# akabeacon_circle_MDBT40.net
KiCad netlist of a schematic drawn in EAGLE
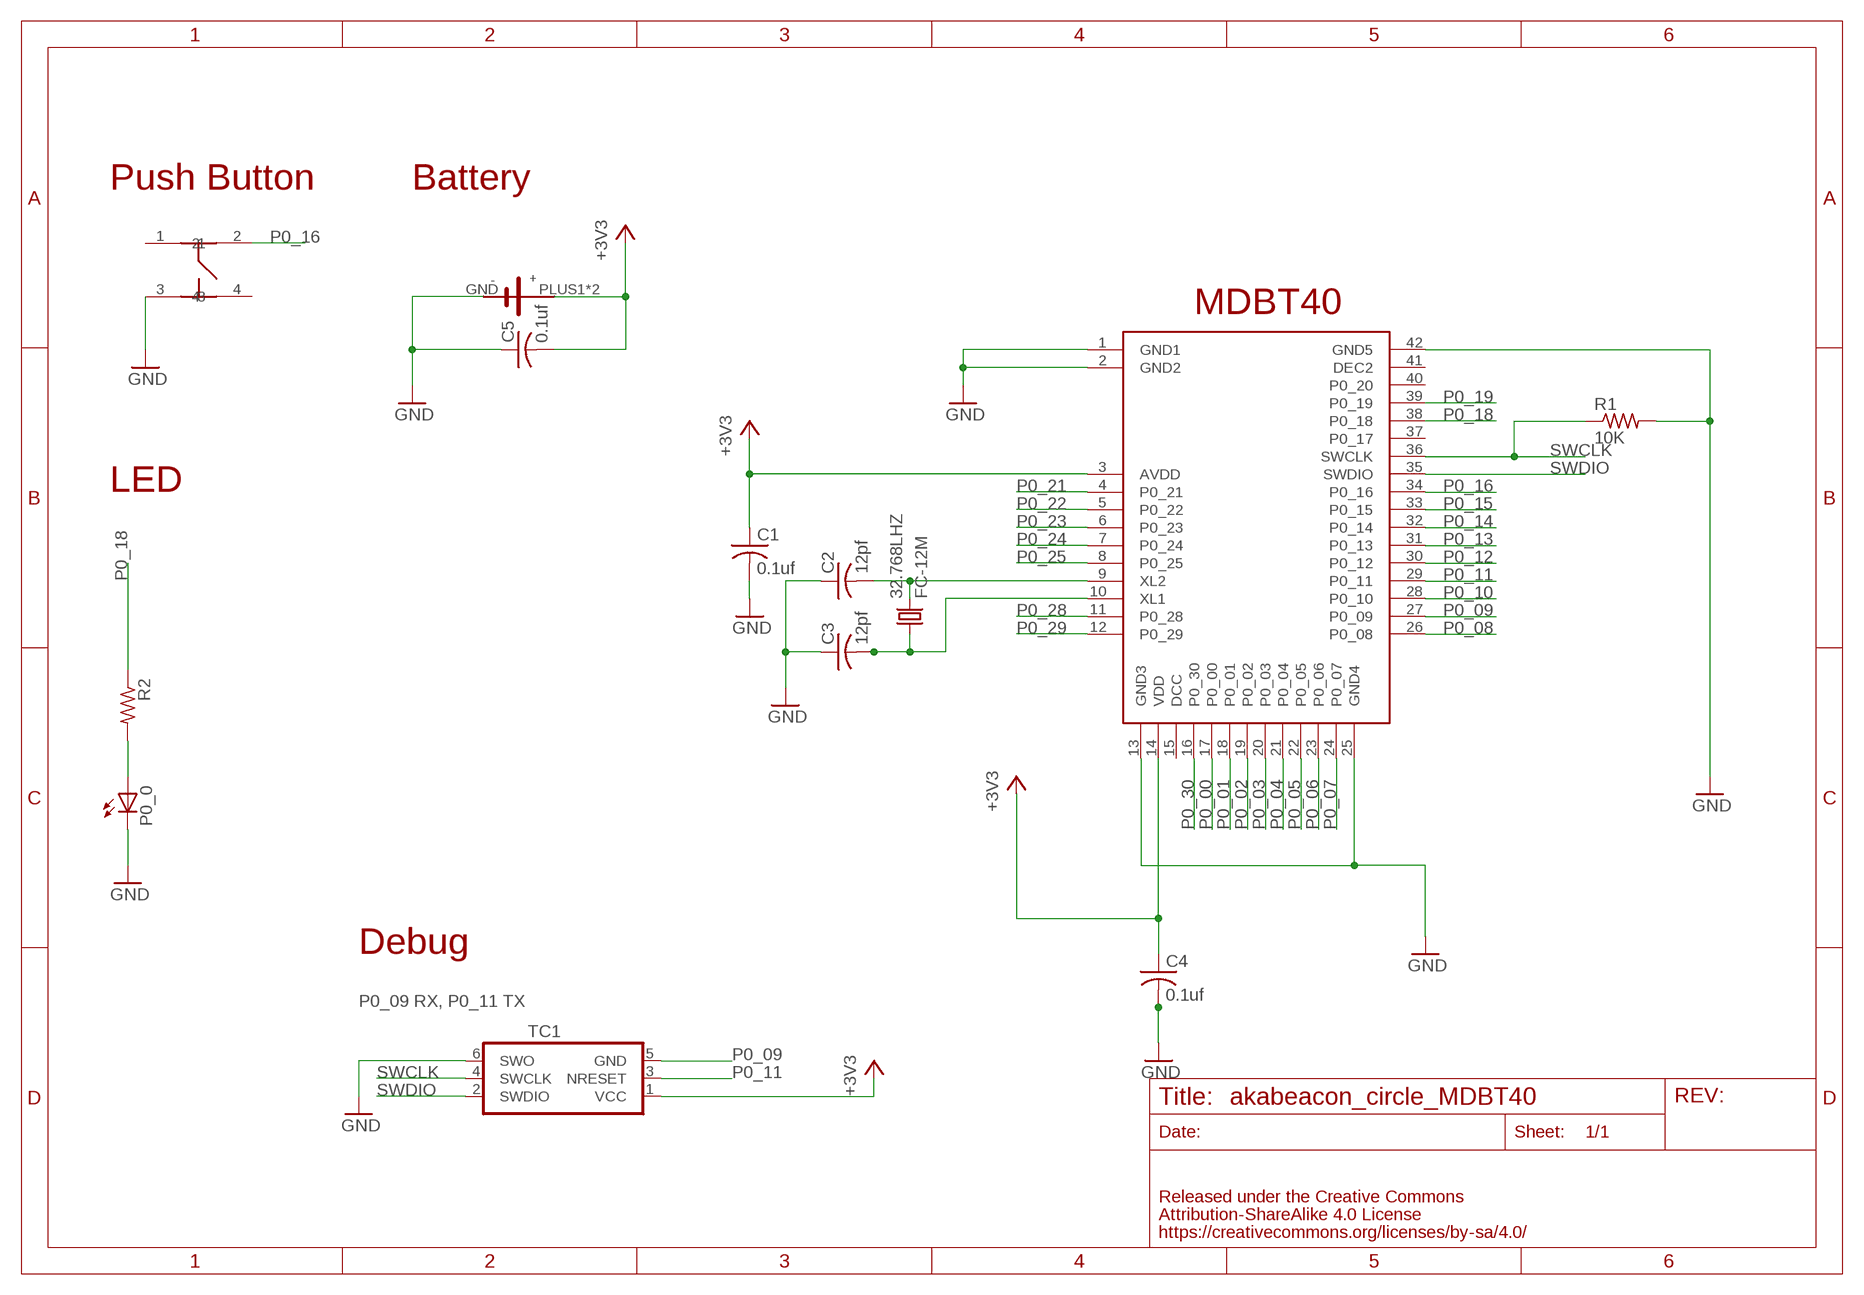
[diagram p0: schematic, sheet 1]

(export (version "E")
  (design (tool "Eeschema 10.0.6"))
  (components
    (comp (ref "32.768LHZ")
      (value "FC-12M")
      (footprint "eagle-import:FC-12M")
      (libsource (lib "eagle-import") (part "FC-12M"))
    )
    (comp (ref "C1")
      (value "0.1uf")
      (footprint "eagle-import:C0603")
      (libsource (lib "eagle-import") (part "C-USC0603"))
    )
    (comp (ref "C2")
      (value "12pf")
      (footprint "eagle-import:C0603")
      (libsource (lib "eagle-import") (part "C-USC0603"))
    )
    (comp (ref "C3")
      (value "12pf")
      (footprint "eagle-import:C0603")
      (libsource (lib "eagle-import") (part "C-USC0603"))
    )
    (comp (ref "C4")
      (value "0.1uf")
      (footprint "eagle-import:C0603")
      (libsource (lib "eagle-import") (part "C-USC0603"))
    )
    (comp (ref "C5")
      (value "0.1uf")
      (footprint "eagle-import:C0603")
      (libsource (lib "eagle-import") (part "C-USC0603"))
    )
    (comp (ref "P0_0")
      (value "LEDCHIP-LED0603")
      (footprint "eagle-import:CHIP-LED0603")
      (libsource (lib "eagle-import") (part "LEDCHIP-LED0603"))
    )
    (comp (ref "R1")
      (value "10K")
      (footprint "eagle-import:R0603")
      (libsource (lib "eagle-import") (part "R-US_R0603"))
    )
    (comp (ref "R2")
      (value "R-US_R0603")
      (footprint "eagle-import:R0603")
      (libsource (lib "eagle-import") (part "R-US_R0603"))
    )
    (comp (ref "TC1")
      (value "TC2030-IDC-NL")
      (footprint "eagle-import:TC2030-IDC-NL")
      (libsource (lib "eagle-import") (part "TC2030-IDC-NL"))
    )
    (comp (ref "U$1")
      (value "RAYTAC-MDBT40")
      (footprint "eagle-import:RAYTAC-MDBT40")
      (libsource (lib "eagle-import") (part "RAYTAC-MDBT40"))
    )
    (comp (ref "U$5")
      (value "SWICTH-4P(KMR2)")
      (footprint "eagle-import:SWITCH-4P(KMR2)")
      (libsource (lib "eagle-import") (part "SWICTH-4P(KMR2)"))
    )
    (comp (ref "U$7")
      (value "CIRCLE-TYPE1")
      (footprint "eagle-import:CIRCLE-TYE1-TC2030")
      (libsource (lib "eagle-import") (part "CIRCLE-TYPE1"))
    )
  )
  (nets
    (net (code "1") (name "+3V3") (class "Default")
      (node (ref "C1") (pin "1") (pinfunction "1_1") (pintype "passive"))
      (node (ref "C4") (pin "1") (pinfunction "1_1") (pintype "passive"))
      (node (ref "C5") (pin "2") (pinfunction "2_2") (pintype "passive"))
      (node (ref "TC1") (pin "1") (pinfunction "VCC_1") (pintype "passive"))
      (node (ref "U$1") (pin "14") (pinfunction "VDD_14") (pintype "bidirectional"))
      (node (ref "U$1") (pin "3") (pinfunction "AVDD_3") (pintype "bidirectional"))
      (node (ref "U$7") (pin "PLUS1") (pinfunction "VCC_PLUS1") (pintype "bidirectional"))
      (node (ref "U$7") (pin "PLUS2") (pinfunction "VCC_PLUS2") (pintype "bidirectional"))
    )
    (net (code "2") (name "/P0_00") (class "Default")
      (node (ref "U$1") (pin "17") (pinfunction "P0_00_17") (pintype "bidirectional"))
    )
    (net (code "3") (name "/P0_01") (class "Default")
      (node (ref "U$1") (pin "18") (pinfunction "P0_01_18") (pintype "bidirectional"))
    )
    (net (code "4") (name "/P0_02") (class "Default")
      (node (ref "U$1") (pin "19") (pinfunction "P0_02_19") (pintype "bidirectional"))
    )
    (net (code "5") (name "/P0_03") (class "Default")
      (node (ref "U$1") (pin "20") (pinfunction "P0_03_20") (pintype "bidirectional"))
    )
    (net (code "6") (name "/P0_04") (class "Default")
      (node (ref "U$1") (pin "21") (pinfunction "P0_04_21") (pintype "bidirectional"))
    )
    (net (code "7") (name "/P0_05") (class "Default")
      (node (ref "U$1") (pin "22") (pinfunction "P0_05_22") (pintype "bidirectional"))
    )
    (net (code "8") (name "/P0_06") (class "Default")
      (node (ref "U$1") (pin "23") (pinfunction "P0_06_23") (pintype "bidirectional"))
    )
    (net (code "9") (name "/P0_07") (class "Default")
      (node (ref "U$1") (pin "24") (pinfunction "P0_07_24") (pintype "bidirectional"))
    )
    (net (code "10") (name "/P0_08") (class "Default")
      (node (ref "U$1") (pin "26") (pinfunction "P0_08_26") (pintype "bidirectional"))
    )
    (net (code "11") (name "/P0_09") (class "Default")
      (node (ref "TC1") (pin "5") (pinfunction "GND_5") (pintype "passive"))
      (node (ref "U$1") (pin "27") (pinfunction "P0_09_27") (pintype "bidirectional"))
    )
    (net (code "12") (name "/P0_10") (class "Default")
      (node (ref "U$1") (pin "28") (pinfunction "P0_10_28") (pintype "bidirectional"))
    )
    (net (code "13") (name "/P0_11") (class "Default")
      (node (ref "TC1") (pin "3") (pinfunction "NRESET_3") (pintype "passive"))
      (node (ref "U$1") (pin "29") (pinfunction "P0_11_29") (pintype "bidirectional"))
    )
    (net (code "14") (name "/P0_12") (class "Default")
      (node (ref "U$1") (pin "30") (pinfunction "P0_12_30") (pintype "bidirectional"))
    )
    (net (code "15") (name "/P0_13") (class "Default")
      (node (ref "U$1") (pin "31") (pinfunction "P0_13_31") (pintype "bidirectional"))
    )
    (net (code "16") (name "/P0_14") (class "Default")
      (node (ref "U$1") (pin "32") (pinfunction "P0_14_32") (pintype "bidirectional"))
    )
    (net (code "17") (name "/P0_15") (class "Default")
      (node (ref "U$1") (pin "33") (pinfunction "P0_15_33") (pintype "bidirectional"))
    )
    (net (code "18") (name "/P0_16") (class "Default")
      (node (ref "U$1") (pin "34") (pinfunction "P0_16_34") (pintype "bidirectional"))
      (node (ref "U$5") (pin "2") (pinfunction "2_2") (pintype "bidirectional"))
    )
    (net (code "19") (name "/P0_18") (class "Default")
      (node (ref "R2") (pin "1") (pinfunction "1_1") (pintype "passive"))
      (node (ref "U$1") (pin "38") (pinfunction "P0_18_38") (pintype "bidirectional"))
    )
    (net (code "20") (name "/P0_19") (class "Default")
      (node (ref "U$1") (pin "39") (pinfunction "P0_19_39") (pintype "bidirectional"))
    )
    (net (code "21") (name "/P0_21") (class "Default")
      (node (ref "U$1") (pin "4") (pinfunction "P0_21_4") (pintype "bidirectional"))
    )
    (net (code "22") (name "/P0_22") (class "Default")
      (node (ref "U$1") (pin "5") (pinfunction "P0_22_5") (pintype "bidirectional"))
    )
    (net (code "23") (name "/P0_23") (class "Default")
      (node (ref "U$1") (pin "6") (pinfunction "P0_23_6") (pintype "bidirectional"))
    )
    (net (code "24") (name "/P0_24") (class "Default")
      (node (ref "U$1") (pin "7") (pinfunction "P0_24_7") (pintype "bidirectional"))
    )
    (net (code "25") (name "/P0_25") (class "Default")
      (node (ref "U$1") (pin "8") (pinfunction "P0_25_8") (pintype "bidirectional"))
    )
    (net (code "26") (name "/P0_28") (class "Default")
      (node (ref "U$1") (pin "11") (pinfunction "P0_28_11") (pintype "bidirectional"))
    )
    (net (code "27") (name "/P0_29") (class "Default")
      (node (ref "U$1") (pin "12") (pinfunction "P0_29_12") (pintype "bidirectional"))
    )
    (net (code "28") (name "/P0_30") (class "Default")
      (node (ref "U$1") (pin "16") (pinfunction "P0_30_16") (pintype "bidirectional"))
    )
    (net (code "29") (name "/SWCLK") (class "Default")
      (node (ref "R1") (pin "1") (pinfunction "1_1") (pintype "passive"))
      (node (ref "TC1") (pin "4") (pinfunction "SWCLK_4") (pintype "passive"))
      (node (ref "U$1") (pin "36") (pinfunction "SWCLK_36") (pintype "bidirectional"))
    )
    (net (code "30") (name "/SWDIO") (class "Default")
      (node (ref "TC1") (pin "2") (pinfunction "SWDIO_2") (pintype "passive"))
      (node (ref "U$1") (pin "35") (pinfunction "SWDIO_35") (pintype "bidirectional"))
    )
    (net (code "31") (name "GND") (class "Default")
      (node (ref "C1") (pin "2") (pinfunction "2_2") (pintype "passive"))
      (node (ref "C2") (pin "1") (pinfunction "1_1") (pintype "passive"))
      (node (ref "C3") (pin "1") (pinfunction "1_1") (pintype "passive"))
      (node (ref "C4") (pin "2") (pinfunction "2_2") (pintype "passive"))
      (node (ref "C5") (pin "1") (pinfunction "1_1") (pintype "passive"))
      (node (ref "P0_0") (pin "C") (pinfunction "C_C") (pintype "passive"))
      (node (ref "R1") (pin "2") (pinfunction "2_2") (pintype "passive"))
      (node (ref "TC1") (pin "6") (pinfunction "SWO_6") (pintype "passive"))
      (node (ref "U$1") (pin "1") (pinfunction "GND1_1") (pintype "bidirectional"))
      (node (ref "U$1") (pin "13") (pinfunction "GND3_13") (pintype "bidirectional"))
      (node (ref "U$1") (pin "2") (pinfunction "GND2_2") (pintype "bidirectional"))
      (node (ref "U$1") (pin "25") (pinfunction "GND4_25") (pintype "bidirectional"))
      (node (ref "U$1") (pin "42") (pinfunction "GND5_42") (pintype "bidirectional"))
      (node (ref "U$5") (pin "3") (pinfunction "3_3") (pintype "bidirectional"))
      (node (ref "U$7") (pin "GND") (pinfunction "GND_GND") (pintype "bidirectional"))
    )
    (net (code "32") (name "Net-(P0_0-PadA)") (class "Default")
      (node (ref "P0_0") (pin "A") (pinfunction "A_A") (pintype "passive"))
      (node (ref "R2") (pin "2") (pinfunction "2_2") (pintype "passive"))
    )
    (net (code "33") (name "Net-(U$1-XL1)") (class "Default")
      (node (ref "32.768LHZ") (pin "1") (pinfunction "1_1") (pintype "passive"))
      (node (ref "C3") (pin "2") (pinfunction "2_2") (pintype "passive"))
      (node (ref "U$1") (pin "10") (pinfunction "XL1_10") (pintype "bidirectional"))
    )
    (net (code "34") (name "Net-(U$1-XL2)") (class "Default")
      (node (ref "32.768LHZ") (pin "2") (pinfunction "2_2") (pintype "passive"))
      (node (ref "C2") (pin "2") (pinfunction "2_2") (pintype "passive"))
      (node (ref "U$1") (pin "9") (pinfunction "XL2_9") (pintype "bidirectional"))
    )
    (net (code "35") (name "unconnected-(U$1-DCC-Pad15)") (class "Default")
      (node (ref "U$1") (pin "15") (pinfunction "DCC_15") (pintype "bidirectional"))
    )
    (net (code "36") (name "unconnected-(U$1-DEC2-Pad41)") (class "Default")
      (node (ref "U$1") (pin "41") (pinfunction "DEC2_41") (pintype "bidirectional"))
    )
    (net (code "37") (name "unconnected-(U$1-P0_17-Pad37)") (class "Default")
      (node (ref "U$1") (pin "37") (pinfunction "P0_17_37") (pintype "bidirectional"))
    )
    (net (code "38") (name "unconnected-(U$1-P0_20-Pad40)") (class "Default")
      (node (ref "U$1") (pin "40") (pinfunction "P0_20_40") (pintype "bidirectional"))
    )
    (net (code "39") (name "unconnected-(U$5-Pad1)") (class "Default")
      (node (ref "U$5") (pin "1") (pinfunction "1_1") (pintype "bidirectional"))
    )
    (net (code "40") (name "unconnected-(U$5-Pad4)") (class "Default")
      (node (ref "U$5") (pin "4") (pinfunction "4_4") (pintype "bidirectional"))
    )
  )
)
